# DisplayPort.net
KiCad netlist of a schematic drawn in Altium Designer
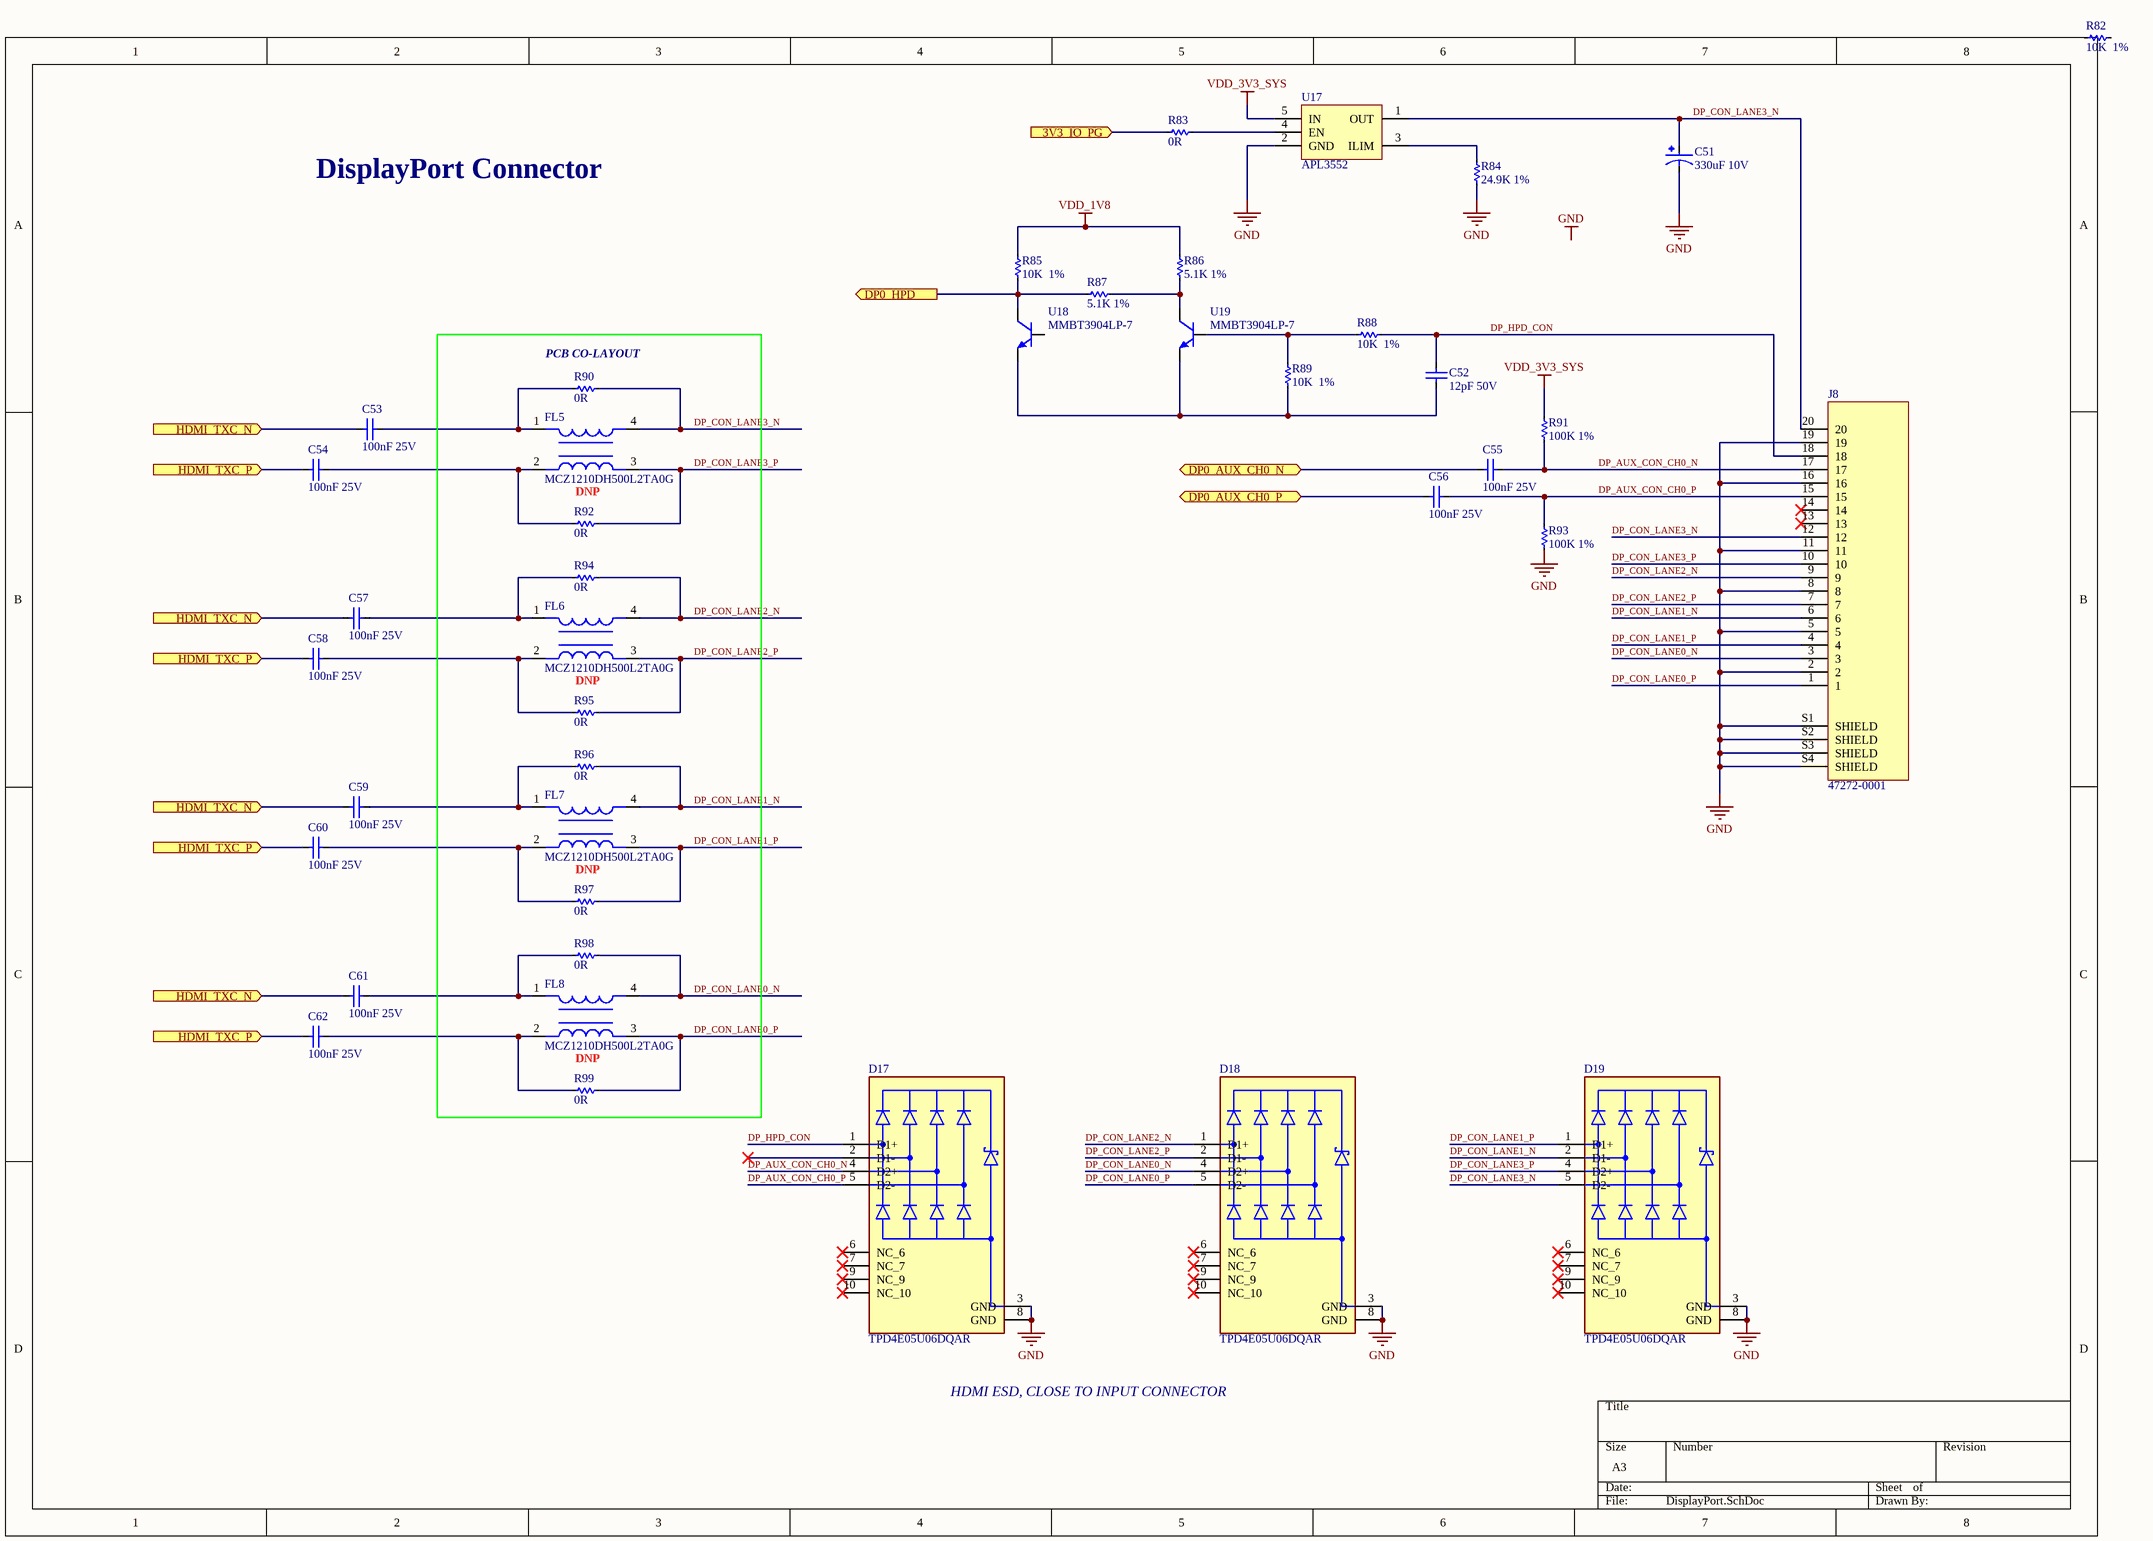
[diagram p0: DisplayPort.SchDoc]

(export (version "E")
  (design (tool "Eeschema 10.0.6"))
  (components
    (comp (ref "C51")
      (value "330uF 10V")
      (footprint "C2917_Tantalum")
      (description "Cap Tant Polymer 330uF 10VDC D CASE 20% (7.3 X 4.3 X 2.8mm) SMD 7343-31 0.025 Ohm 105C T/R")
      (fields
        (field (name "MANUFACTURER") "Vishay Sprague")
        (field (name "MANUFACTURER PART NUMBER") "T55D337M010C0025")
      )
      (libsource (lib "GM_Capacitor") (part "T55D337M010C0025"))
    )
    (comp (ref "C52")
      (value "12pF 50V")
      (footprint "C0402")
      (description "0402 12 pF 50 V ±5 % Tolerance NP0 SMT Multilayer Ceramic Capacitor")
      (fields
        (field (name "MANUFACTURER") "Yageo")
        (field (name "MANUFACTURER PART NUMBER") "CC0402JRNPO9BN120")
      )
      (libsource (lib "GM_Capacitor") (part "CC0402JRNPO9BN120"))
    )
    (comp (ref "C53")
      (value "100nF 25V")
      (footprint "C0402")
      (description "0402 100 nF 25 V ±10 % Tolerance X7R Surface Mount Multilayer Ceramic Capacitor")
      (fields
        (field (name "MANUFACTURER") "Kyocera AVX")
        (field (name "MANUFACTURER PART NUMBER") "04023C104KAT2A")
      )
      (libsource (lib "GM_Altium_Library") (part "04023C104KAT2A"))
    )
    (comp (ref "C54")
      (value "100nF 25V")
      (footprint "C0402")
      (description "0402 100 nF 25 V ±10 % Tolerance X7R Surface Mount Multilayer Ceramic Capacitor")
      (fields
        (field (name "MANUFACTURER") "Kyocera AVX")
        (field (name "MANUFACTURER PART NUMBER") "04023C104KAT2A")
      )
      (libsource (lib "GM_Altium_Library") (part "04023C104KAT2A"))
    )
    (comp (ref "C55")
      (value "100nF 25V")
      (footprint "C0402")
      (description "0402 100 nF 25 V ±10 % Tolerance X7R Surface Mount Multilayer Ceramic Capacitor")
      (fields
        (field (name "MANUFACTURER") "Kyocera AVX")
        (field (name "MANUFACTURER PART NUMBER") "04023C104KAT2A")
      )
      (libsource (lib "GM_Altium_Library") (part "04023C104KAT2A"))
    )
    (comp (ref "C56")
      (value "100nF 25V")
      (footprint "C0402")
      (description "0402 100 nF 25 V ±10 % Tolerance X7R Surface Mount Multilayer Ceramic Capacitor")
      (fields
        (field (name "MANUFACTURER") "Kyocera AVX")
        (field (name "MANUFACTURER PART NUMBER") "04023C104KAT2A")
      )
      (libsource (lib "GM_Altium_Library") (part "04023C104KAT2A"))
    )
    (comp (ref "C57")
      (value "100nF 25V")
      (footprint "C0402")
      (description "0402 100 nF 25 V ±10 % Tolerance X7R Surface Mount Multilayer Ceramic Capacitor")
      (fields
        (field (name "MANUFACTURER") "Kyocera AVX")
        (field (name "MANUFACTURER PART NUMBER") "04023C104KAT2A")
      )
      (libsource (lib "GM_Altium_Library") (part "04023C104KAT2A"))
    )
    (comp (ref "C58")
      (value "100nF 25V")
      (footprint "C0402")
      (description "0402 100 nF 25 V ±10 % Tolerance X7R Surface Mount Multilayer Ceramic Capacitor")
      (fields
        (field (name "MANUFACTURER") "Kyocera AVX")
        (field (name "MANUFACTURER PART NUMBER") "04023C104KAT2A")
      )
      (libsource (lib "GM_Altium_Library") (part "04023C104KAT2A"))
    )
    (comp (ref "C59")
      (value "100nF 25V")
      (footprint "C0402")
      (description "0402 100 nF 25 V ±10 % Tolerance X7R Surface Mount Multilayer Ceramic Capacitor")
      (fields
        (field (name "MANUFACTURER") "Kyocera AVX")
        (field (name "MANUFACTURER PART NUMBER") "04023C104KAT2A")
      )
      (libsource (lib "GM_Altium_Library") (part "04023C104KAT2A"))
    )
    (comp (ref "C60")
      (value "100nF 25V")
      (footprint "C0402")
      (description "0402 100 nF 25 V ±10 % Tolerance X7R Surface Mount Multilayer Ceramic Capacitor")
      (fields
        (field (name "MANUFACTURER") "Kyocera AVX")
        (field (name "MANUFACTURER PART NUMBER") "04023C104KAT2A")
      )
      (libsource (lib "GM_Altium_Library") (part "04023C104KAT2A"))
    )
    (comp (ref "C61")
      (value "100nF 25V")
      (footprint "C0402")
      (description "0402 100 nF 25 V ±10 % Tolerance X7R Surface Mount Multilayer Ceramic Capacitor")
      (fields
        (field (name "MANUFACTURER") "Kyocera AVX")
        (field (name "MANUFACTURER PART NUMBER") "04023C104KAT2A")
      )
      (libsource (lib "GM_Altium_Library") (part "04023C104KAT2A"))
    )
    (comp (ref "C62")
      (value "100nF 25V")
      (footprint "C0402")
      (description "0402 100 nF 25 V ±10 % Tolerance X7R Surface Mount Multilayer Ceramic Capacitor")
      (fields
        (field (name "MANUFACTURER") "Kyocera AVX")
        (field (name "MANUFACTURER PART NUMBER") "04023C104KAT2A")
      )
      (libsource (lib "GM_Altium_Library") (part "04023C104KAT2A"))
    )
    (comp (ref "D17")
      (value "TPD4E05U06DQAR")
      (footprint "TPD4E05U06DQAR")
      (description "Quad 0.5-pF, 5.5-V, ±12-kV ESD protection diode for USB, HDMI & High Speed Interfaces")
      (fields (field (name "MANUFACTURER") "Texas Instruments"))
      (libsource (lib "GM_Altium_Library") (part "TPD4E05U06DQAR"))
    )
    (comp (ref "D18")
      (value "TPD4E05U06DQAR")
      (footprint "TPD4E05U06DQAR")
      (description "Quad 0.5-pF, 5.5-V, ±12-kV ESD protection diode for USB, HDMI & High Speed Interfaces")
      (fields (field (name "MANUFACTURER") "Texas Instruments"))
      (libsource (lib "GM_Altium_Library") (part "TPD4E05U06DQAR"))
    )
    (comp (ref "D19")
      (value "TPD4E05U06DQAR")
      (footprint "TPD4E05U06DQAR")
      (description "Quad 0.5-pF, 5.5-V, ±12-kV ESD protection diode for USB, HDMI & High Speed Interfaces")
      (fields (field (name "MANUFACTURER") "Texas Instruments"))
      (libsource (lib "GM_Altium_Library") (part "TPD4E05U06DQAR"))
    )
    (comp (ref "FL5")
      (value "MCZ1210DH500L2TA0G")
      (footprint "MCZ1210DH500L2TA0G")
      (description "2 Line Common Mode Choke Surface Mount 50 Ohms 100mA DCR 2.5Ohm")
      (fields (field (name "MANUFACTURER") "TDK"))
      (libsource (lib "GM_Filter") (part "MCZ1210DH500L2TA0G"))
    )
    (comp (ref "FL6")
      (value "MCZ1210DH500L2TA0G")
      (footprint "MCZ1210DH500L2TA0G")
      (description "2 Line Common Mode Choke Surface Mount 50 Ohms 100mA DCR 2.5Ohm")
      (fields (field (name "MANUFACTURER") "TDK"))
      (libsource (lib "GM_Filter") (part "MCZ1210DH500L2TA0G"))
    )
    (comp (ref "FL7")
      (value "MCZ1210DH500L2TA0G")
      (footprint "MCZ1210DH500L2TA0G")
      (description "2 Line Common Mode Choke Surface Mount 50 Ohms 100mA DCR 2.5Ohm")
      (fields (field (name "MANUFACTURER") "TDK"))
      (libsource (lib "GM_Filter") (part "MCZ1210DH500L2TA0G"))
    )
    (comp (ref "FL8")
      (value "MCZ1210DH500L2TA0G")
      (footprint "MCZ1210DH500L2TA0G")
      (description "2 Line Common Mode Choke Surface Mount 50 Ohms 100mA DCR 2.5Ohm")
      (fields (field (name "MANUFACTURER") "TDK"))
      (libsource (lib "GM_Filter") (part "MCZ1210DH500L2TA0G"))
    )
    (comp (ref "J8")
      (value "47272-0001")
      (footprint "47272-0001")
      (description "Conn Display Port RCP 20 POS 0.5mm Solder RA SMD 20 Terminal 1 Port DisplayPort Embossed T/R")
      (fields (field (name "MANUFACTURER") "Molex"))
      (libsource (lib "GM_Connector") (part "47272-0001"))
    )
    (comp (ref "R82")
      (value "10K  1%")
      (footprint "R0402")
      (description "Res General Purpose Thick Film 0402 10K Ohm 1% 1/16W ±100ppm/°C Molded SMD Paper T/R")
      (fields
        (field (name "MANUFACTURER") "Yageo")
        (field (name "MANUFACTURER PART NUMBER") "RC0402FR-0710KP")
      )
      (libsource (lib "GM_Altium_Library") (part "RC0402FR-0710KP"))
    )
    (comp (ref "R83")
      (value "0R")
      (footprint "R0402")
      (description "RC Series 0402 0.063 W 0 Ohm Jumper Surface Mount Thick Film Chip Resistor")
      (fields
        (field (name "MANUFACTURER") "Yageo")
        (field (name "MANUFACTURER PART NUMBER") "RC0402FR-070RL")
      )
      (libsource (lib "GM_Altium_Library") (part "RC0402FR-070RL"))
    )
    (comp (ref "R84")
      (value "24.9K 1%")
      (footprint "R0402")
      (description "Res Thick Film 0402 24.9K Ohm 1% 1/16W ±100ppm/°C Molded SMD Paper T/R")
      (fields
        (field (name "MANUFACTURER") "Yageo")
        (field (name "MANUFACTURER PART NUMBER") "RC0402FR-0724K9L")
      )
      (libsource (lib "GM_Altium_Library") (part "RC0402FR-0724K9L"))
    )
    (comp (ref "R85")
      (value "10K  1%")
      (footprint "R0402")
      (description "Res General Purpose Thick Film 0402 10K Ohm 1% 1/16W ±100ppm/°C Molded SMD Paper T/R")
      (fields
        (field (name "MANUFACTURER") "Yageo")
        (field (name "MANUFACTURER PART NUMBER") "RC0402FR-0710KP")
      )
      (libsource (lib "GM_Altium_Library") (part "RC0402FR-0710KP"))
    )
    (comp (ref "R86")
      (value "5.1K 1%")
      (footprint "R0402")
      (description "Res Thick Film 1.0 x 0.5 mm 5.1K Ohm 1% 0.063W(1/16W) 100ppm/ C Molded SMD Paper T/R")
      (fields
        (field (name "MANUFACTURER") "Yageo")
        (field (name "MANUFACTURER PART NUMBER") "RC0402FR-075K1L")
      )
      (libsource (lib "GM_Altium_Library") (part "RC0402FR-075K1L"))
    )
    (comp (ref "R87")
      (value "5.1K 1%")
      (footprint "R0402")
      (description "Res Thick Film 1.0 x 0.5 mm 5.1K Ohm 1% 0.063W(1/16W) 100ppm/ C Molded SMD Paper T/R")
      (fields
        (field (name "MANUFACTURER") "Yageo")
        (field (name "MANUFACTURER PART NUMBER") "RC0402FR-075K1L")
      )
      (libsource (lib "GM_Altium_Library") (part "RC0402FR-075K1L"))
    )
    (comp (ref "R88")
      (value "10K  1%")
      (footprint "R0402")
      (description "Res General Purpose Thick Film 0402 10K Ohm 1% 1/16W ±100ppm/°C Molded SMD Paper T/R")
      (fields
        (field (name "MANUFACTURER") "Yageo")
        (field (name "MANUFACTURER PART NUMBER") "RC0402FR-0710KP")
      )
      (libsource (lib "GM_Altium_Library") (part "RC0402FR-0710KP"))
    )
    (comp (ref "R89")
      (value "10K  1%")
      (footprint "R0402")
      (description "Res General Purpose Thick Film 0402 10K Ohm 1% 1/16W ±100ppm/°C Molded SMD Paper T/R")
      (fields
        (field (name "MANUFACTURER") "Yageo")
        (field (name "MANUFACTURER PART NUMBER") "RC0402FR-0710KP")
      )
      (libsource (lib "GM_Altium_Library") (part "RC0402FR-0710KP"))
    )
    (comp (ref "R90")
      (value "0R")
      (footprint "R0402")
      (description "Res Jumper Thick Film 0402 0 Ohm 5% 1/16W Molded SMD Paper T/R")
      (fields
        (field (name "MANUFACTURER") "Yageo")
        (field (name "MANUFACTURER PART NUMBER") "RC0402JR-070RP")
      )
      (libsource (lib "GM_Altium_Library") (part "RC0402JR-070RP"))
    )
    (comp (ref "R91")
      (value "100K 1%")
      (footprint "R0402")
      (description "RES SMD 100K OHM 1% 1/16W 0402")
      (fields
        (field (name "MANUFACTURER") "Yageo")
        (field (name "MANUFACTURER PART NUMBER") "RC0402FR-07100KL")
      )
      (libsource (lib "GM_Altium_Library") (part "RC0402FR-07100KL"))
    )
    (comp (ref "R92")
      (value "0R")
      (footprint "R0402")
      (description "Res Jumper Thick Film 0402 0 Ohm 5% 1/16W Molded SMD Paper T/R")
      (fields
        (field (name "MANUFACTURER") "Yageo")
        (field (name "MANUFACTURER PART NUMBER") "RC0402JR-070RP")
      )
      (libsource (lib "GM_Altium_Library") (part "RC0402JR-070RP"))
    )
    (comp (ref "R93")
      (value "100K 1%")
      (footprint "R0402")
      (description "RES SMD 100K OHM 1% 1/16W 0402")
      (fields
        (field (name "MANUFACTURER") "Yageo")
        (field (name "MANUFACTURER PART NUMBER") "RC0402FR-07100KL")
      )
      (libsource (lib "GM_Altium_Library") (part "RC0402FR-07100KL"))
    )
    (comp (ref "R94")
      (value "0R")
      (footprint "R0402")
      (description "Res Jumper Thick Film 0402 0 Ohm 5% 1/16W Molded SMD Paper T/R")
      (fields
        (field (name "MANUFACTURER") "Yageo")
        (field (name "MANUFACTURER PART NUMBER") "RC0402JR-070RP")
      )
      (libsource (lib "GM_Altium_Library") (part "RC0402JR-070RP"))
    )
    (comp (ref "R95")
      (value "0R")
      (footprint "R0402")
      (description "Res Jumper Thick Film 0402 0 Ohm 5% 1/16W Molded SMD Paper T/R")
      (fields
        (field (name "MANUFACTURER") "Yageo")
        (field (name "MANUFACTURER PART NUMBER") "RC0402JR-070RP")
      )
      (libsource (lib "GM_Altium_Library") (part "RC0402JR-070RP"))
    )
    (comp (ref "R96")
      (value "0R")
      (footprint "R0402")
      (description "Res Jumper Thick Film 0402 0 Ohm 5% 1/16W Molded SMD Paper T/R")
      (fields
        (field (name "MANUFACTURER") "Yageo")
        (field (name "MANUFACTURER PART NUMBER") "RC0402JR-070RP")
      )
      (libsource (lib "GM_Altium_Library") (part "RC0402JR-070RP"))
    )
    (comp (ref "R97")
      (value "0R")
      (footprint "R0402")
      (description "Res Jumper Thick Film 0402 0 Ohm 5% 1/16W Molded SMD Paper T/R")
      (fields
        (field (name "MANUFACTURER") "Yageo")
        (field (name "MANUFACTURER PART NUMBER") "RC0402JR-070RP")
      )
      (libsource (lib "GM_Altium_Library") (part "RC0402JR-070RP"))
    )
    (comp (ref "R98")
      (value "0R")
      (footprint "R0402")
      (description "Res Jumper Thick Film 0402 0 Ohm 5% 1/16W Molded SMD Paper T/R")
      (fields
        (field (name "MANUFACTURER") "Yageo")
        (field (name "MANUFACTURER PART NUMBER") "RC0402JR-070RP")
      )
      (libsource (lib "GM_Altium_Library") (part "RC0402JR-070RP"))
    )
    (comp (ref "R99")
      (value "0R")
      (footprint "R0402")
      (description "Res Jumper Thick Film 0402 0 Ohm 5% 1/16W Molded SMD Paper T/R")
      (fields
        (field (name "MANUFACTURER") "Yageo")
        (field (name "MANUFACTURER PART NUMBER") "RC0402JR-070RP")
      )
      (libsource (lib "GM_Altium_Library") (part "RC0402JR-070RP"))
    )
    (comp (ref "U17")
      (value "APL3552")
      (footprint "SOT23-5")
      (description "The APL3552 series of power switches integrate a 62mW N-channel MOSFET.")
      (libsource (lib "GM_Altium_Library") (part "APL3552"))
    )
    (comp (ref "U18")
      (value "MMBT3904LP-7")
      (footprint "DFN1006-3")
      (description "TRANS NPN 40V 0.2A DFN1006-3")
      (fields (field (name "MANUFACTURER") "Diodes"))
      (libsource (lib "GM_Altium_Library") (part "MMBT3904LP-7"))
    )
    (comp (ref "U19")
      (value "MMBT3904LP-7")
      (footprint "DFN1006-3")
      (description "TRANS NPN 40V 0.2A DFN1006-3")
      (fields (field (name "MANUFACTURER") "Diodes"))
      (libsource (lib "GM_Altium_Library") (part "MMBT3904LP-7"))
    )
  )
  (nets
    (net (code "1") (name "/3V3_IO_PG") (class "Default")
      (node (ref "R83") (pin "1") (pinfunction "1_1") (pintype "passive"))
    )
    (net (code "2") (name "/DP0_AUX_CH0_N") (class "Default")
      (node (ref "C55") (pin "1") (pinfunction "1_1") (pintype "passive"))
    )
    (net (code "3") (name "/DP0_AUX_CH0_P") (class "Default")
      (node (ref "C56") (pin "1") (pinfunction "1_1") (pintype "passive"))
    )
    (net (code "4") (name "/DP0_HPD") (class "Default")
      (node (ref "R85") (pin "1") (pinfunction "1_1") (pintype "passive"))
      (node (ref "R87") (pin "1") (pinfunction "1_1") (pintype "passive"))
      (node (ref "U18") (pin "3") (pinfunction "C_3") (pintype "passive"))
    )
    (net (code "5") (name "/DP_AUX_CON_CH0_N") (class "Default")
      (node (ref "C55") (pin "2") (pinfunction "2_2") (pintype "passive"))
      (node (ref "D17") (pin "4") (pinfunction "D2+_4") (pintype "passive"))
      (node (ref "J8") (pin "17") (pinfunction "17_17") (pintype "passive"))
      (node (ref "R91") (pin "1") (pinfunction "1_1") (pintype "passive"))
    )
    (net (code "6") (name "/DP_AUX_CON_CH0_P") (class "Default")
      (node (ref "C56") (pin "2") (pinfunction "2_2") (pintype "passive"))
      (node (ref "D17") (pin "5") (pinfunction "D2-_5") (pintype "passive"))
      (node (ref "J8") (pin "15") (pinfunction "15_15") (pintype "passive"))
      (node (ref "R93") (pin "2") (pinfunction "2_2") (pintype "passive"))
    )
    (net (code "7") (name "/DP_CON_LANE0_N") (class "Default")
      (node (ref "D18") (pin "4") (pinfunction "D2+_4") (pintype "passive"))
      (node (ref "FL8") (pin "4") (pinfunction "4_4") (pintype "passive"))
      (node (ref "J8") (pin "3") (pinfunction "3_3") (pintype "passive"))
      (node (ref "R98") (pin "2") (pinfunction "2_2") (pintype "passive"))
    )
    (net (code "8") (name "/DP_CON_LANE0_P") (class "Default")
      (node (ref "D18") (pin "5") (pinfunction "D2-_5") (pintype "passive"))
      (node (ref "FL8") (pin "3") (pinfunction "3_3") (pintype "passive"))
      (node (ref "J8") (pin "1") (pinfunction "1_1") (pintype "passive"))
      (node (ref "R99") (pin "2") (pinfunction "2_2") (pintype "passive"))
    )
    (net (code "9") (name "/DP_CON_LANE1_N") (class "Default")
      (node (ref "D19") (pin "2") (pinfunction "D1-_2") (pintype "passive"))
      (node (ref "FL7") (pin "4") (pinfunction "4_4") (pintype "passive"))
      (node (ref "J8") (pin "6") (pinfunction "6_6") (pintype "passive"))
      (node (ref "R96") (pin "2") (pinfunction "2_2") (pintype "passive"))
    )
    (net (code "10") (name "/DP_CON_LANE1_P") (class "Default")
      (node (ref "D19") (pin "1") (pinfunction "D1+_1") (pintype "passive"))
      (node (ref "FL7") (pin "3") (pinfunction "3_3") (pintype "passive"))
      (node (ref "J8") (pin "4") (pinfunction "4_4") (pintype "passive"))
      (node (ref "R97") (pin "2") (pinfunction "2_2") (pintype "passive"))
    )
    (net (code "11") (name "/DP_CON_LANE2_N") (class "Default")
      (node (ref "D18") (pin "1") (pinfunction "D1+_1") (pintype "passive"))
      (node (ref "FL6") (pin "4") (pinfunction "4_4") (pintype "passive"))
      (node (ref "J8") (pin "9") (pinfunction "9_9") (pintype "passive"))
      (node (ref "R94") (pin "2") (pinfunction "2_2") (pintype "passive"))
    )
    (net (code "12") (name "/DP_CON_LANE2_P") (class "Default")
      (node (ref "D18") (pin "2") (pinfunction "D1-_2") (pintype "passive"))
      (node (ref "FL6") (pin "3") (pinfunction "3_3") (pintype "passive"))
      (node (ref "J8") (pin "7") (pinfunction "7_7") (pintype "passive"))
      (node (ref "R95") (pin "2") (pinfunction "2_2") (pintype "passive"))
    )
    (net (code "13") (name "/DP_CON_LANE3_N") (class "Default")
      (node (ref "C51") (pin "1") (pinfunction "A_1") (pintype "passive"))
      (node (ref "D19") (pin "5") (pinfunction "D2-_5") (pintype "passive"))
      (node (ref "FL5") (pin "4") (pinfunction "4_4") (pintype "passive"))
      (node (ref "J8") (pin "12") (pinfunction "12_12") (pintype "passive"))
      (node (ref "J8") (pin "20") (pinfunction "20_20") (pintype "passive"))
      (node (ref "R90") (pin "2") (pinfunction "2_2") (pintype "passive"))
      (node (ref "U17") (pin "1") (pinfunction "OUT_1") (pintype "passive"))
    )
    (net (code "14") (name "/DP_CON_LANE3_P") (class "Default")
      (node (ref "D19") (pin "4") (pinfunction "D2+_4") (pintype "passive"))
      (node (ref "FL5") (pin "3") (pinfunction "3_3") (pintype "passive"))
      (node (ref "J8") (pin "10") (pinfunction "10_10") (pintype "passive"))
      (node (ref "R92") (pin "2") (pinfunction "2_2") (pintype "passive"))
    )
    (net (code "15") (name "/DP_HPD_CON") (class "Default")
      (node (ref "C52") (pin "2") (pinfunction "2_2") (pintype "passive"))
      (node (ref "D17") (pin "1") (pinfunction "D1+_1") (pintype "passive"))
      (node (ref "J8") (pin "18") (pinfunction "18_18") (pintype "passive"))
      (node (ref "R88") (pin "2") (pinfunction "2_2") (pintype "passive"))
    )
    (net (code "16") (name "/HDMI_TXC_N") (class "Default")
      (node (ref "C53") (pin "1") (pinfunction "1_1") (pintype "passive"))
      (node (ref "C57") (pin "1") (pinfunction "1_1") (pintype "passive"))
      (node (ref "C59") (pin "1") (pinfunction "1_1") (pintype "passive"))
      (node (ref "C61") (pin "1") (pinfunction "1_1") (pintype "passive"))
    )
    (net (code "17") (name "/HDMI_TXC_P") (class "Default")
      (node (ref "C54") (pin "1") (pinfunction "1_1") (pintype "passive"))
      (node (ref "C58") (pin "1") (pinfunction "1_1") (pintype "passive"))
      (node (ref "C60") (pin "1") (pinfunction "1_1") (pintype "passive"))
      (node (ref "C62") (pin "1") (pinfunction "1_1") (pintype "passive"))
    )
    (net (code "18") (name "GND") (class "Default")
      (node (ref "C51") (pin "2") (pinfunction "C_2") (pintype "passive"))
      (node (ref "D17") (pin "3") (pinfunction "GND_3") (pintype "power_in"))
      (node (ref "D17") (pin "8") (pinfunction "GND_8") (pintype "power_in"))
      (node (ref "D18") (pin "3") (pinfunction "GND_3") (pintype "power_in"))
      (node (ref "D18") (pin "8") (pinfunction "GND_8") (pintype "power_in"))
      (node (ref "D19") (pin "3") (pinfunction "GND_3") (pintype "power_in"))
      (node (ref "D19") (pin "8") (pinfunction "GND_8") (pintype "power_in"))
      (node (ref "J8") (pin "11") (pinfunction "11_11") (pintype "passive"))
      (node (ref "J8") (pin "16") (pinfunction "16_16") (pintype "passive"))
      (node (ref "J8") (pin "19") (pinfunction "19_19") (pintype "passive"))
      (node (ref "J8") (pin "2") (pinfunction "2_2") (pintype "passive"))
      (node (ref "J8") (pin "5") (pinfunction "5_5") (pintype "passive"))
      (node (ref "J8") (pin "8") (pinfunction "8_8") (pintype "passive"))
      (node (ref "J8") (pin "S1") (pinfunction "SHIELD_S1") (pintype "passive"))
      (node (ref "J8") (pin "S2") (pinfunction "SHIELD_S2") (pintype "passive"))
      (node (ref "J8") (pin "S3") (pinfunction "SHIELD_S3") (pintype "passive"))
      (node (ref "J8") (pin "S4") (pinfunction "SHIELD_S4") (pintype "passive"))
      (node (ref "R84") (pin "1") (pinfunction "1_1") (pintype "passive"))
      (node (ref "R93") (pin "1") (pinfunction "1_1") (pintype "passive"))
      (node (ref "U17") (pin "2") (pinfunction "GND_2") (pintype "power_in"))
    )
    (net (code "19") (name "Net-(C53-Pad2)") (class "Default")
      (node (ref "C53") (pin "2") (pinfunction "2_2") (pintype "passive"))
      (node (ref "FL5") (pin "1") (pinfunction "1_1") (pintype "passive"))
      (node (ref "R90") (pin "1") (pinfunction "1_1") (pintype "passive"))
    )
    (net (code "20") (name "Net-(C54-Pad2)") (class "Default")
      (node (ref "C54") (pin "2") (pinfunction "2_2") (pintype "passive"))
      (node (ref "FL5") (pin "2") (pinfunction "2_2") (pintype "passive"))
      (node (ref "R92") (pin "1") (pinfunction "1_1") (pintype "passive"))
    )
    (net (code "21") (name "Net-(C57-Pad2)") (class "Default")
      (node (ref "C57") (pin "2") (pinfunction "2_2") (pintype "passive"))
      (node (ref "FL6") (pin "1") (pinfunction "1_1") (pintype "passive"))
      (node (ref "R94") (pin "1") (pinfunction "1_1") (pintype "passive"))
    )
    (net (code "22") (name "Net-(C58-Pad2)") (class "Default")
      (node (ref "C58") (pin "2") (pinfunction "2_2") (pintype "passive"))
      (node (ref "FL6") (pin "2") (pinfunction "2_2") (pintype "passive"))
      (node (ref "R95") (pin "1") (pinfunction "1_1") (pintype "passive"))
    )
    (net (code "23") (name "Net-(C59-Pad2)") (class "Default")
      (node (ref "C59") (pin "2") (pinfunction "2_2") (pintype "passive"))
      (node (ref "FL7") (pin "1") (pinfunction "1_1") (pintype "passive"))
      (node (ref "R96") (pin "1") (pinfunction "1_1") (pintype "passive"))
    )
    (net (code "24") (name "Net-(C60-Pad2)") (class "Default")
      (node (ref "C60") (pin "2") (pinfunction "2_2") (pintype "passive"))
      (node (ref "FL7") (pin "2") (pinfunction "2_2") (pintype "passive"))
      (node (ref "R97") (pin "1") (pinfunction "1_1") (pintype "passive"))
    )
    (net (code "25") (name "Net-(C61-Pad2)") (class "Default")
      (node (ref "C61") (pin "2") (pinfunction "2_2") (pintype "passive"))
      (node (ref "FL8") (pin "1") (pinfunction "1_1") (pintype "passive"))
      (node (ref "R98") (pin "1") (pinfunction "1_1") (pintype "passive"))
    )
    (net (code "26") (name "Net-(C62-Pad2)") (class "Default")
      (node (ref "C62") (pin "2") (pinfunction "2_2") (pintype "passive"))
      (node (ref "FL8") (pin "2") (pinfunction "2_2") (pintype "passive"))
      (node (ref "R99") (pin "1") (pinfunction "1_1") (pintype "passive"))
    )
    (net (code "27") (name "Net-(U17-EN)") (class "Default")
      (node (ref "R83") (pin "2") (pinfunction "2_2") (pintype "passive"))
      (node (ref "U17") (pin "4") (pinfunction "EN_4") (pintype "passive"))
    )
    (net (code "28") (name "Net-(U17-ILIM)") (class "Default")
      (node (ref "R84") (pin "2") (pinfunction "2_2") (pintype "passive"))
      (node (ref "U17") (pin "3") (pinfunction "ILIM_3") (pintype "passive"))
    )
    (net (code "29") (name "Net-(U18-E)") (class "Default")
      (node (ref "C52") (pin "1") (pinfunction "1_1") (pintype "passive"))
      (node (ref "R89") (pin "1") (pinfunction "1_1") (pintype "passive"))
      (node (ref "U18") (pin "2") (pinfunction "E_2") (pintype "passive"))
      (node (ref "U19") (pin "2") (pinfunction "E_2") (pintype "passive"))
    )
    (net (code "30") (name "Net-(U19-B)") (class "Default")
      (node (ref "R88") (pin "1") (pinfunction "1_1") (pintype "passive"))
      (node (ref "R89") (pin "2") (pinfunction "2_2") (pintype "passive"))
      (node (ref "U19") (pin "1") (pinfunction "B_1") (pintype "passive"))
    )
    (net (code "31") (name "Net-(U19-C)") (class "Default")
      (node (ref "R86") (pin "1") (pinfunction "1_1") (pintype "passive"))
      (node (ref "R87") (pin "2") (pinfunction "2_2") (pintype "passive"))
      (node (ref "U19") (pin "3") (pinfunction "C_3") (pintype "passive"))
    )
    (net (code "32") (name "VDD_1V8") (class "Default")
      (node (ref "R85") (pin "2") (pinfunction "2_2") (pintype "passive"))
      (node (ref "R86") (pin "2") (pinfunction "2_2") (pintype "passive"))
    )
    (net (code "33") (name "VDD_3V3_SYS") (class "Default")
      (node (ref "R91") (pin "2") (pinfunction "2_2") (pintype "passive"))
      (node (ref "U17") (pin "5") (pinfunction "IN_5") (pintype "power_in"))
    )
    (net (code "34") (name "unconnected-(D17-D1--Pad2)") (class "Default")
      (node (ref "D17") (pin "2") (pinfunction "D1-_2") (pintype "passive+no_connect"))
    )
    (net (code "35") (name "unconnected-(D17-NC_6-Pad6)") (class "Default")
      (node (ref "D17") (pin "6") (pinfunction "NC_6_6") (pintype "passive+no_connect"))
    )
    (net (code "36") (name "unconnected-(D17-NC_7-Pad7)") (class "Default")
      (node (ref "D17") (pin "7") (pinfunction "NC_7_7") (pintype "passive+no_connect"))
    )
    (net (code "37") (name "unconnected-(D17-NC_9-Pad9)") (class "Default")
      (node (ref "D17") (pin "9") (pinfunction "NC_9_9") (pintype "passive+no_connect"))
    )
    (net (code "38") (name "unconnected-(D17-NC_10-Pad10)") (class "Default")
      (node (ref "D17") (pin "10") (pinfunction "NC_10_10") (pintype "passive+no_connect"))
    )
    (net (code "39") (name "unconnected-(D18-NC_6-Pad6)") (class "Default")
      (node (ref "D18") (pin "6") (pinfunction "NC_6_6") (pintype "passive+no_connect"))
    )
    (net (code "40") (name "unconnected-(D18-NC_7-Pad7)") (class "Default")
      (node (ref "D18") (pin "7") (pinfunction "NC_7_7") (pintype "passive+no_connect"))
    )
    (net (code "41") (name "unconnected-(D18-NC_9-Pad9)") (class "Default")
      (node (ref "D18") (pin "9") (pinfunction "NC_9_9") (pintype "passive+no_connect"))
    )
    (net (code "42") (name "unconnected-(D18-NC_10-Pad10)") (class "Default")
      (node (ref "D18") (pin "10") (pinfunction "NC_10_10") (pintype "passive+no_connect"))
    )
    (net (code "43") (name "unconnected-(D19-NC_6-Pad6)") (class "Default")
      (node (ref "D19") (pin "6") (pinfunction "NC_6_6") (pintype "passive+no_connect"))
    )
    (net (code "44") (name "unconnected-(D19-NC_7-Pad7)") (class "Default")
      (node (ref "D19") (pin "7") (pinfunction "NC_7_7") (pintype "passive+no_connect"))
    )
    (net (code "45") (name "unconnected-(D19-NC_9-Pad9)") (class "Default")
      (node (ref "D19") (pin "9") (pinfunction "NC_9_9") (pintype "passive+no_connect"))
    )
    (net (code "46") (name "unconnected-(D19-NC_10-Pad10)") (class "Default")
      (node (ref "D19") (pin "10") (pinfunction "NC_10_10") (pintype "passive+no_connect"))
    )
    (net (code "47") (name "unconnected-(J8-Pad13)") (class "Default")
      (node (ref "J8") (pin "13") (pinfunction "13_13") (pintype "passive+no_connect"))
    )
    (net (code "48") (name "unconnected-(J8-Pad14)") (class "Default")
      (node (ref "J8") (pin "14") (pinfunction "14_14") (pintype "passive+no_connect"))
    )
    (net (code "49") (name "unconnected-(R82-Pad1)") (class "Default")
      (node (ref "R82") (pin "1") (pinfunction "1_1") (pintype "passive"))
    )
    (net (code "50") (name "unconnected-(R82-Pad2)") (class "Default")
      (node (ref "R82") (pin "2") (pinfunction "2_2") (pintype "passive"))
    )
    (net (code "51") (name "unconnected-(U18-B-Pad1)") (class "Default")
      (node (ref "U18") (pin "1") (pinfunction "B_1") (pintype "passive"))
    )
  )
)
